# IO_Bottom_Board.net
KiCad netlist of a schematic drawn in EAGLE
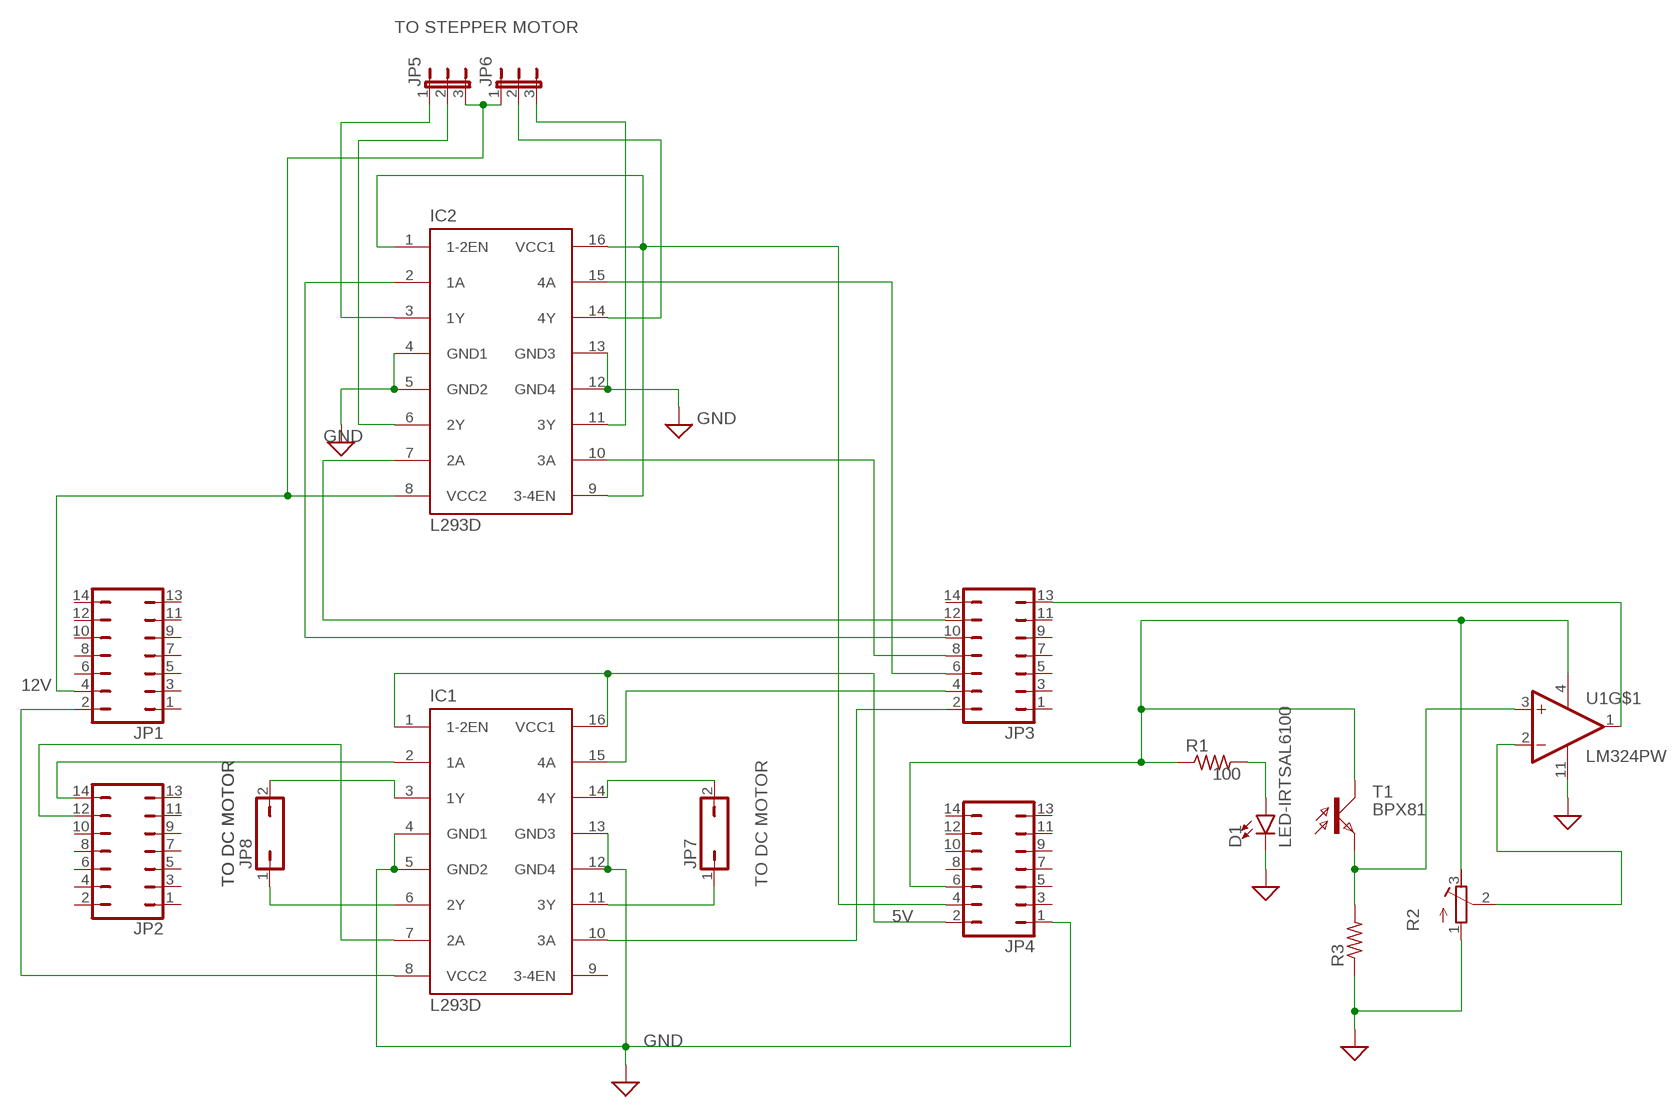
[diagram p0: schematic, sheet 1]

(export (version "E")
  (design (tool "Eeschema 10.0.6"))
  (components
    (comp (ref "D1")
      (value "LED-IRTSAL6100")
      (footprint "eagle-import:LED_5MM")
      (libsource (lib "eagle-import") (part "LED-IRTSAL6100"))
    )
    (comp (ref "IC1")
      (value "L293D")
      (footprint "eagle-import:DIL16")
      (libsource (lib "eagle-import") (part "L293D"))
    )
    (comp (ref "IC2")
      (value "L293D")
      (footprint "eagle-import:DIL16")
      (libsource (lib "eagle-import") (part "L293D"))
    )
    (comp (ref "JP1")
      (value "JP7Q")
      (footprint "eagle-import:JP7Q")
      (libsource (lib "eagle-import") (part "JP7Q"))
    )
    (comp (ref "JP2")
      (value "JP7Q")
      (footprint "eagle-import:JP7Q")
      (libsource (lib "eagle-import") (part "JP7Q"))
    )
    (comp (ref "JP3")
      (value "JP7Q")
      (footprint "eagle-import:JP7Q")
      (libsource (lib "eagle-import") (part "JP7Q"))
    )
    (comp (ref "JP4")
      (value "JP7Q")
      (footprint "eagle-import:JP7Q")
      (libsource (lib "eagle-import") (part "JP7Q"))
    )
    (comp (ref "JP5")
      (value "JP2E")
      (footprint "eagle-import:JP2")
      (libsource (lib "eagle-import") (part "JP2E"))
    )
    (comp (ref "JP6")
      (value "JP2E")
      (footprint "eagle-import:JP2")
      (libsource (lib "eagle-import") (part "JP2E"))
    )
    (comp (ref "JP7")
      (value "JP1Q")
      (footprint "eagle-import:JP1")
      (libsource (lib "eagle-import") (part "JP1Q"))
    )
    (comp (ref "JP8")
      (value "JP1Q")
      (footprint "eagle-import:JP1")
      (libsource (lib "eagle-import") (part "JP1Q"))
    )
    (comp (ref "R1")
      (value "R-US_0204/2V")
      (footprint "eagle-import:0204V")
      (libsource (lib "eagle-import") (part "R-US_0204/2V"))
    )
    (comp (ref "R2")
      (value "R-TRIMM3214W")
      (footprint "eagle-import:RTRIM3214W")
      (libsource (lib "eagle-import") (part "R-TRIMM3214W"))
    )
    (comp (ref "R3")
      (value "R-US_0204/2V")
      (footprint "eagle-import:0204V")
      (libsource (lib "eagle-import") (part "R-US_0204/2V"))
    )
    (comp (ref "T1")
      (value "BPX81")
      (footprint "eagle-import:BPX81")
      (libsource (lib "eagle-import") (part "BPX81"))
    )
    (comp (ref "U1")
      (value "LM324PW")
      (footprint "eagle-import:SOP65P640X120-14N")
      (fields (field (name "MF") "Texas Instruments"))
      (libsource (lib "eagle-import") (part "LM324PW"))
    )
  )
  (nets
    (net (code "1") (name "/5V") (class "Default")
      (node (ref "IC1") (pin "8") (pinfunction "VCC2_8") (pintype "power_in"))
      (node (ref "JP1") (pin "2") (pinfunction "2_2") (pintype "passive"))
    )
    (net (code "2") (name "Net-(D1-PadA)") (class "Default")
      (node (ref "D1") (pin "A") (pinfunction "A_A") (pintype "passive"))
      (node (ref "R1") (pin "2") (pinfunction "2_2") (pintype "passive"))
    )
    (net (code "3") (name "Net-(IC1-1-2EN)") (class "Default")
      (node (ref "IC1") (pin "1") (pinfunction "1-2EN_1") (pintype "input"))
      (node (ref "IC1") (pin "16") (pinfunction "VCC1_16") (pintype "power_in"))
      (node (ref "JP4") (pin "2") (pinfunction "2_2") (pintype "passive"))
    )
    (net (code "4") (name "Net-(IC1-1A)") (class "Default")
      (node (ref "IC1") (pin "2") (pinfunction "1A_2") (pintype "input"))
      (node (ref "JP2") (pin "14") (pinfunction "14_14") (pintype "passive"))
    )
    (net (code "5") (name "Net-(IC1-1Y)") (class "Default")
      (node (ref "IC1") (pin "3") (pinfunction "1Y_3") (pintype "output"))
      (node (ref "JP8") (pin "2") (pinfunction "2_2") (pintype "passive"))
    )
    (net (code "6") (name "Net-(IC1-2A)") (class "Default")
      (node (ref "IC1") (pin "7") (pinfunction "2A_7") (pintype "input"))
      (node (ref "JP2") (pin "12") (pinfunction "12_12") (pintype "passive"))
    )
    (net (code "7") (name "Net-(IC1-2Y)") (class "Default")
      (node (ref "IC1") (pin "6") (pinfunction "2Y_6") (pintype "output"))
      (node (ref "JP8") (pin "1") (pinfunction "1_1") (pintype "passive"))
    )
    (net (code "8") (name "Net-(IC1-3A)") (class "Default")
      (node (ref "IC1") (pin "10") (pinfunction "3A_10") (pintype "input"))
      (node (ref "JP3") (pin "2") (pinfunction "2_2") (pintype "passive"))
    )
    (net (code "9") (name "Net-(IC1-3Y)") (class "Default")
      (node (ref "IC1") (pin "11") (pinfunction "3Y_11") (pintype "output"))
      (node (ref "JP7") (pin "1") (pinfunction "1_1") (pintype "passive"))
    )
    (net (code "10") (name "Net-(IC1-4A)") (class "Default")
      (node (ref "IC1") (pin "15") (pinfunction "4A_15") (pintype "input"))
      (node (ref "JP3") (pin "4") (pinfunction "4_4") (pintype "passive"))
    )
    (net (code "11") (name "Net-(IC1-4Y)") (class "Default")
      (node (ref "IC1") (pin "14") (pinfunction "4Y_14") (pintype "output"))
      (node (ref "JP7") (pin "2") (pinfunction "2_2") (pintype "passive"))
    )
    (net (code "12") (name "Net-(IC2-1-2EN)") (class "Default")
      (node (ref "IC2") (pin "1") (pinfunction "1-2EN_1") (pintype "input"))
      (node (ref "IC2") (pin "16") (pinfunction "VCC1_16") (pintype "power_in"))
      (node (ref "IC2") (pin "9") (pinfunction "3-4EN_9") (pintype "input"))
      (node (ref "JP4") (pin "4") (pinfunction "4_4") (pintype "passive"))
    )
    (net (code "13") (name "Net-(IC2-1A)") (class "Default")
      (node (ref "IC2") (pin "2") (pinfunction "1A_2") (pintype "input"))
      (node (ref "JP3") (pin "10") (pinfunction "10_10") (pintype "passive"))
    )
    (net (code "14") (name "Net-(IC2-1Y)") (class "Default")
      (node (ref "IC2") (pin "3") (pinfunction "1Y_3") (pintype "output"))
      (node (ref "JP5") (pin "1") (pinfunction "1_1") (pintype "passive"))
    )
    (net (code "15") (name "Net-(IC2-2A)") (class "Default")
      (node (ref "IC2") (pin "7") (pinfunction "2A_7") (pintype "input"))
      (node (ref "JP3") (pin "12") (pinfunction "12_12") (pintype "passive"))
    )
    (net (code "16") (name "Net-(IC2-2Y)") (class "Default")
      (node (ref "IC2") (pin "6") (pinfunction "2Y_6") (pintype "output"))
      (node (ref "JP5") (pin "2") (pinfunction "2_2") (pintype "passive"))
    )
    (net (code "17") (name "Net-(IC2-3A)") (class "Default")
      (node (ref "IC2") (pin "10") (pinfunction "3A_10") (pintype "input"))
      (node (ref "JP3") (pin "8") (pinfunction "8_8") (pintype "passive"))
    )
    (net (code "18") (name "Net-(IC2-3Y)") (class "Default")
      (node (ref "IC2") (pin "11") (pinfunction "3Y_11") (pintype "output"))
      (node (ref "JP6") (pin "3") (pinfunction "3_3") (pintype "passive"))
    )
    (net (code "19") (name "Net-(IC2-4A)") (class "Default")
      (node (ref "IC2") (pin "15") (pinfunction "4A_15") (pintype "input"))
      (node (ref "JP3") (pin "6") (pinfunction "6_6") (pintype "passive"))
    )
    (net (code "20") (name "Net-(IC2-4Y)") (class "Default")
      (node (ref "IC2") (pin "14") (pinfunction "4Y_14") (pintype "output"))
      (node (ref "JP6") (pin "2") (pinfunction "2_2") (pintype "passive"))
    )
    (net (code "21") (name "Net-(IC2-VCC2)") (class "Default")
      (node (ref "IC2") (pin "8") (pinfunction "VCC2_8") (pintype "power_in"))
      (node (ref "JP1") (pin "4") (pinfunction "4_4") (pintype "passive"))
      (node (ref "JP5") (pin "3") (pinfunction "3_3") (pintype "passive"))
      (node (ref "JP6") (pin "1") (pinfunction "1_1") (pintype "passive"))
    )
    (net (code "22") (name "Net-(R2-E)") (class "Default")
      (node (ref "JP4") (pin "6") (pinfunction "6_6") (pintype "passive"))
      (node (ref "R1") (pin "1") (pinfunction "1_1") (pintype "passive"))
      (node (ref "R2") (pin "3") (pinfunction "E_3") (pintype "passive"))
      (node (ref "T1") (pin "C") (pinfunction "C_C") (pintype "passive"))
      (node (ref "U1") (pin "4") (pinfunction "VCC_4") (pintype "power_in"))
    )
    (net (code "23") (name "Net-(R2-S)") (class "Default")
      (node (ref "R2") (pin "2") (pinfunction "S_2") (pintype "passive"))
      (node (ref "U1") (pin "2") (pinfunction "-IN1_2") (pintype "input"))
    )
    (net (code "24") (name "Net-(U1A-+IN1)") (class "Default")
      (node (ref "R3") (pin "2") (pinfunction "2_2") (pintype "passive"))
      (node (ref "T1") (pin "E") (pinfunction "E_E") (pintype "passive"))
      (node (ref "U1") (pin "3") (pinfunction "+IN1_3") (pintype "input"))
    )
    (net (code "25") (name "Net-(U1A-OUT1)") (class "Default")
      (node (ref "JP3") (pin "13") (pinfunction "13_13") (pintype "passive"))
      (node (ref "U1") (pin "1") (pinfunction "OUT1_1") (pintype "output"))
    )
    (net (code "26") (name "SUP") (class "Default")
      (node (ref "D1") (pin "K") (pinfunction "C_K") (pintype "passive"))
      (node (ref "IC1") (pin "12") (pinfunction "GND4_12") (pintype "power_in"))
      (node (ref "IC1") (pin "13") (pinfunction "GND3_13") (pintype "power_in"))
      (node (ref "IC1") (pin "4") (pinfunction "GND1_4") (pintype "power_in"))
      (node (ref "IC1") (pin "5") (pinfunction "GND2_5") (pintype "power_in"))
      (node (ref "IC2") (pin "12") (pinfunction "GND4_12") (pintype "power_in"))
      (node (ref "IC2") (pin "13") (pinfunction "GND3_13") (pintype "power_in"))
      (node (ref "IC2") (pin "4") (pinfunction "GND1_4") (pintype "power_in"))
      (node (ref "IC2") (pin "5") (pinfunction "GND2_5") (pintype "power_in"))
      (node (ref "JP4") (pin "1") (pinfunction "1_1") (pintype "passive"))
      (node (ref "R2") (pin "1") (pinfunction "A_1") (pintype "passive"))
      (node (ref "R3") (pin "1") (pinfunction "1_1") (pintype "passive"))
      (node (ref "U1") (pin "11") (pinfunction "GND_11") (pintype "power_in"))
    )
    (net (code "27") (name "unconnected-(IC1-3-4EN-Pad9)") (class "Default")
      (node (ref "IC1") (pin "9") (pinfunction "3-4EN_9") (pintype "input"))
    )
    (net (code "28") (name "unconnected-(JP1-Pad1)") (class "Default")
      (node (ref "JP1") (pin "1") (pinfunction "1_1") (pintype "passive"))
    )
    (net (code "29") (name "unconnected-(JP1-Pad3)") (class "Default")
      (node (ref "JP1") (pin "3") (pinfunction "3_3") (pintype "passive"))
    )
    (net (code "30") (name "unconnected-(JP1-Pad5)") (class "Default")
      (node (ref "JP1") (pin "5") (pinfunction "5_5") (pintype "passive"))
    )
    (net (code "31") (name "unconnected-(JP1-Pad6)") (class "Default")
      (node (ref "JP1") (pin "6") (pinfunction "6_6") (pintype "passive"))
    )
    (net (code "32") (name "unconnected-(JP1-Pad7)") (class "Default")
      (node (ref "JP1") (pin "7") (pinfunction "7_7") (pintype "passive"))
    )
    (net (code "33") (name "unconnected-(JP1-Pad8)") (class "Default")
      (node (ref "JP1") (pin "8") (pinfunction "8_8") (pintype "passive"))
    )
    (net (code "34") (name "unconnected-(JP1-Pad9)") (class "Default")
      (node (ref "JP1") (pin "9") (pinfunction "9_9") (pintype "passive"))
    )
    (net (code "35") (name "unconnected-(JP1-Pad10)") (class "Default")
      (node (ref "JP1") (pin "10") (pinfunction "10_10") (pintype "passive"))
    )
    (net (code "36") (name "unconnected-(JP1-Pad11)") (class "Default")
      (node (ref "JP1") (pin "11") (pinfunction "11_11") (pintype "passive"))
    )
    (net (code "37") (name "unconnected-(JP1-Pad12)") (class "Default")
      (node (ref "JP1") (pin "12") (pinfunction "12_12") (pintype "passive"))
    )
    (net (code "38") (name "unconnected-(JP1-Pad13)") (class "Default")
      (node (ref "JP1") (pin "13") (pinfunction "13_13") (pintype "passive"))
    )
    (net (code "39") (name "unconnected-(JP1-Pad14)") (class "Default")
      (node (ref "JP1") (pin "14") (pinfunction "14_14") (pintype "passive"))
    )
    (net (code "40") (name "unconnected-(JP2-Pad1)") (class "Default")
      (node (ref "JP2") (pin "1") (pinfunction "1_1") (pintype "passive"))
    )
    (net (code "41") (name "unconnected-(JP2-Pad2)") (class "Default")
      (node (ref "JP2") (pin "2") (pinfunction "2_2") (pintype "passive"))
    )
    (net (code "42") (name "unconnected-(JP2-Pad3)") (class "Default")
      (node (ref "JP2") (pin "3") (pinfunction "3_3") (pintype "passive"))
    )
    (net (code "43") (name "unconnected-(JP2-Pad4)") (class "Default")
      (node (ref "JP2") (pin "4") (pinfunction "4_4") (pintype "passive"))
    )
    (net (code "44") (name "unconnected-(JP2-Pad5)") (class "Default")
      (node (ref "JP2") (pin "5") (pinfunction "5_5") (pintype "passive"))
    )
    (net (code "45") (name "unconnected-(JP2-Pad6)") (class "Default")
      (node (ref "JP2") (pin "6") (pinfunction "6_6") (pintype "passive"))
    )
    (net (code "46") (name "unconnected-(JP2-Pad7)") (class "Default")
      (node (ref "JP2") (pin "7") (pinfunction "7_7") (pintype "passive"))
    )
    (net (code "47") (name "unconnected-(JP2-Pad8)") (class "Default")
      (node (ref "JP2") (pin "8") (pinfunction "8_8") (pintype "passive"))
    )
    (net (code "48") (name "unconnected-(JP2-Pad9)") (class "Default")
      (node (ref "JP2") (pin "9") (pinfunction "9_9") (pintype "passive"))
    )
    (net (code "49") (name "unconnected-(JP2-Pad10)") (class "Default")
      (node (ref "JP2") (pin "10") (pinfunction "10_10") (pintype "passive"))
    )
    (net (code "50") (name "unconnected-(JP2-Pad11)") (class "Default")
      (node (ref "JP2") (pin "11") (pinfunction "11_11") (pintype "passive"))
    )
    (net (code "51") (name "unconnected-(JP2-Pad13)") (class "Default")
      (node (ref "JP2") (pin "13") (pinfunction "13_13") (pintype "passive"))
    )
    (net (code "52") (name "unconnected-(JP3-Pad1)") (class "Default")
      (node (ref "JP3") (pin "1") (pinfunction "1_1") (pintype "passive"))
    )
    (net (code "53") (name "unconnected-(JP3-Pad3)") (class "Default")
      (node (ref "JP3") (pin "3") (pinfunction "3_3") (pintype "passive"))
    )
    (net (code "54") (name "unconnected-(JP3-Pad5)") (class "Default")
      (node (ref "JP3") (pin "5") (pinfunction "5_5") (pintype "passive"))
    )
    (net (code "55") (name "unconnected-(JP3-Pad7)") (class "Default")
      (node (ref "JP3") (pin "7") (pinfunction "7_7") (pintype "passive"))
    )
    (net (code "56") (name "unconnected-(JP3-Pad9)") (class "Default")
      (node (ref "JP3") (pin "9") (pinfunction "9_9") (pintype "passive"))
    )
    (net (code "57") (name "unconnected-(JP3-Pad11)") (class "Default")
      (node (ref "JP3") (pin "11") (pinfunction "11_11") (pintype "passive"))
    )
    (net (code "58") (name "unconnected-(JP3-Pad14)") (class "Default")
      (node (ref "JP3") (pin "14") (pinfunction "14_14") (pintype "passive"))
    )
    (net (code "59") (name "unconnected-(JP4-Pad3)") (class "Default")
      (node (ref "JP4") (pin "3") (pinfunction "3_3") (pintype "passive"))
    )
    (net (code "60") (name "unconnected-(JP4-Pad5)") (class "Default")
      (node (ref "JP4") (pin "5") (pinfunction "5_5") (pintype "passive"))
    )
    (net (code "61") (name "unconnected-(JP4-Pad7)") (class "Default")
      (node (ref "JP4") (pin "7") (pinfunction "7_7") (pintype "passive"))
    )
    (net (code "62") (name "unconnected-(JP4-Pad8)") (class "Default")
      (node (ref "JP4") (pin "8") (pinfunction "8_8") (pintype "passive"))
    )
    (net (code "63") (name "unconnected-(JP4-Pad9)") (class "Default")
      (node (ref "JP4") (pin "9") (pinfunction "9_9") (pintype "passive"))
    )
    (net (code "64") (name "unconnected-(JP4-Pad10)") (class "Default")
      (node (ref "JP4") (pin "10") (pinfunction "10_10") (pintype "passive"))
    )
    (net (code "65") (name "unconnected-(JP4-Pad11)") (class "Default")
      (node (ref "JP4") (pin "11") (pinfunction "11_11") (pintype "passive"))
    )
    (net (code "66") (name "unconnected-(JP4-Pad12)") (class "Default")
      (node (ref "JP4") (pin "12") (pinfunction "12_12") (pintype "passive"))
    )
    (net (code "67") (name "unconnected-(JP4-Pad13)") (class "Default")
      (node (ref "JP4") (pin "13") (pinfunction "13_13") (pintype "passive"))
    )
    (net (code "68") (name "unconnected-(JP4-Pad14)") (class "Default")
      (node (ref "JP4") (pin "14") (pinfunction "14_14") (pintype "passive"))
    )
  )
)
